# followLineSensor.net
KiCad netlist of a schematic drawn in EAGLE
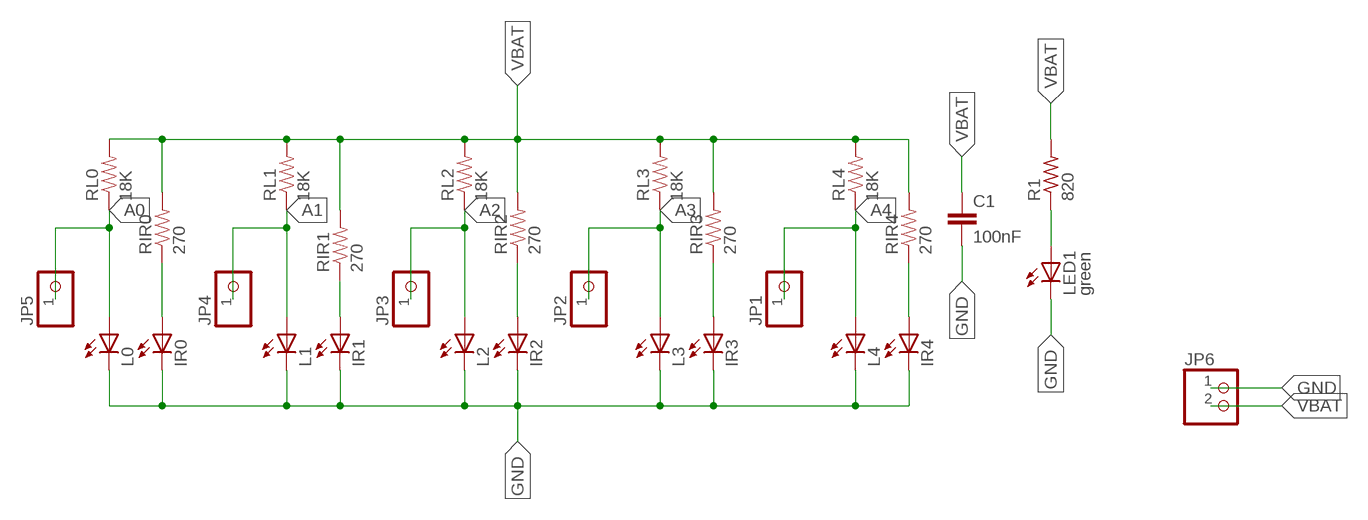
[diagram p0: schematic, sheet 1]

(export (version "E")
  (design (tool "Eeschema 10.0.6"))
  (components
    (comp (ref "C1")
      (value "100nF")
      (footprint "eagle-import:C0805")
      (libsource (lib "eagle-import") (part "C-EUC0805"))
    )
    (comp (ref "IR0")
      (value "LED5MM")
      (footprint "eagle-import:LED5MM")
      (libsource (lib "eagle-import") (part "LED5MM"))
    )
    (comp (ref "IR1")
      (value "LED5MM")
      (footprint "eagle-import:LED5MM")
      (libsource (lib "eagle-import") (part "LED5MM"))
    )
    (comp (ref "IR2")
      (value "LED5MM")
      (footprint "eagle-import:LED5MM")
      (libsource (lib "eagle-import") (part "LED5MM"))
    )
    (comp (ref "IR3")
      (value "LED5MM")
      (footprint "eagle-import:LED5MM")
      (libsource (lib "eagle-import") (part "LED5MM"))
    )
    (comp (ref "IR4")
      (value "LED5MM")
      (footprint "eagle-import:LED5MM")
      (libsource (lib "eagle-import") (part "LED5MM"))
    )
    (comp (ref "JP1")
      (value "PINHD-1X1")
      (footprint "eagle-import:1X01")
      (libsource (lib "eagle-import") (part "PINHD-1X1"))
    )
    (comp (ref "JP2")
      (value "PINHD-1X1")
      (footprint "eagle-import:1X01")
      (libsource (lib "eagle-import") (part "PINHD-1X1"))
    )
    (comp (ref "JP3")
      (value "PINHD-1X1")
      (footprint "eagle-import:1X01")
      (libsource (lib "eagle-import") (part "PINHD-1X1"))
    )
    (comp (ref "JP4")
      (value "PINHD-1X1")
      (footprint "eagle-import:1X01")
      (libsource (lib "eagle-import") (part "PINHD-1X1"))
    )
    (comp (ref "JP5")
      (value "PINHD-1X1")
      (footprint "eagle-import:1X01")
      (libsource (lib "eagle-import") (part "PINHD-1X1"))
    )
    (comp (ref "JP6")
      (value "PINHD-1X2")
      (footprint "eagle-import:1X02")
      (libsource (lib "eagle-import") (part "PINHD-1X2"))
    )
    (comp (ref "L0")
      (value "LED5MM")
      (footprint "eagle-import:LED5MM")
      (libsource (lib "eagle-import") (part "LED5MM"))
    )
    (comp (ref "L1")
      (value "LED5MM")
      (footprint "eagle-import:LED5MM")
      (libsource (lib "eagle-import") (part "LED5MM"))
    )
    (comp (ref "L2")
      (value "LED5MM")
      (footprint "eagle-import:LED5MM")
      (libsource (lib "eagle-import") (part "LED5MM"))
    )
    (comp (ref "L3")
      (value "LED5MM")
      (footprint "eagle-import:LED5MM")
      (libsource (lib "eagle-import") (part "LED5MM"))
    )
    (comp (ref "L4")
      (value "LED5MM")
      (footprint "eagle-import:LED5MM")
      (libsource (lib "eagle-import") (part "LED5MM"))
    )
    (comp (ref "LED1")
      (value "green")
      (footprint "eagle-import:SML0805")
      (libsource (lib "eagle-import") (part "LEDSML0805"))
    )
    (comp (ref "R1")
      (value "820")
      (footprint "eagle-import:R0805")
      (libsource (lib "eagle-import") (part "R-US_R0805"))
    )
    (comp (ref "RIR0")
      (value "270")
      (footprint "eagle-import:1206")
      (libsource (lib "eagle-import") (part "RESISTOR1206"))
    )
    (comp (ref "RIR1")
      (value "270")
      (footprint "eagle-import:1206")
      (libsource (lib "eagle-import") (part "RESISTOR1206"))
    )
    (comp (ref "RIR2")
      (value "270")
      (footprint "eagle-import:1206")
      (libsource (lib "eagle-import") (part "RESISTOR1206"))
    )
    (comp (ref "RIR3")
      (value "270")
      (footprint "eagle-import:1206")
      (libsource (lib "eagle-import") (part "RESISTOR1206"))
    )
    (comp (ref "RIR4")
      (value "270")
      (footprint "eagle-import:1206")
      (libsource (lib "eagle-import") (part "RESISTOR1206"))
    )
    (comp (ref "RL0")
      (value "18K")
      (footprint "eagle-import:1206")
      (libsource (lib "eagle-import") (part "RESISTOR1206"))
    )
    (comp (ref "RL1")
      (value "18K")
      (footprint "eagle-import:1206")
      (libsource (lib "eagle-import") (part "RESISTOR1206"))
    )
    (comp (ref "RL2")
      (value "18K")
      (footprint "eagle-import:1206")
      (libsource (lib "eagle-import") (part "RESISTOR1206"))
    )
    (comp (ref "RL3")
      (value "18K")
      (footprint "eagle-import:1206")
      (libsource (lib "eagle-import") (part "RESISTOR1206"))
    )
    (comp (ref "RL4")
      (value "18K")
      (footprint "eagle-import:1206")
      (libsource (lib "eagle-import") (part "RESISTOR1206"))
    )
  )
  (nets
    (net (code "1") (name "A0") (class "Default")
      (node (ref "JP5") (pin "1") (pinfunction "1_1") (pintype "passive"))
      (node (ref "L0") (pin "A") (pinfunction "A_A") (pintype "passive"))
      (node (ref "RL0") (pin "1") (pinfunction "1_1") (pintype "passive"))
    )
    (net (code "2") (name "A1") (class "Default")
      (node (ref "JP4") (pin "1") (pinfunction "1_1") (pintype "passive"))
      (node (ref "L1") (pin "A") (pinfunction "A_A") (pintype "passive"))
      (node (ref "RL1") (pin "1") (pinfunction "1_1") (pintype "passive"))
    )
    (net (code "3") (name "A2") (class "Default")
      (node (ref "JP3") (pin "1") (pinfunction "1_1") (pintype "passive"))
      (node (ref "L2") (pin "A") (pinfunction "A_A") (pintype "passive"))
      (node (ref "RL2") (pin "1") (pinfunction "1_1") (pintype "passive"))
    )
    (net (code "4") (name "A3") (class "Default")
      (node (ref "JP2") (pin "1") (pinfunction "1_1") (pintype "passive"))
      (node (ref "L3") (pin "A") (pinfunction "A_A") (pintype "passive"))
      (node (ref "RL3") (pin "1") (pinfunction "1_1") (pintype "passive"))
    )
    (net (code "5") (name "A4") (class "Default")
      (node (ref "JP1") (pin "1") (pinfunction "1_1") (pintype "passive"))
      (node (ref "L4") (pin "A") (pinfunction "A_A") (pintype "passive"))
      (node (ref "RL4") (pin "1") (pinfunction "1_1") (pintype "passive"))
    )
    (net (code "6") (name "GND") (class "Default")
      (node (ref "C1") (pin "2") (pinfunction "2_2") (pintype "passive"))
      (node (ref "IR0") (pin "K") (pinfunction "C_K") (pintype "passive"))
      (node (ref "IR1") (pin "K") (pinfunction "C_K") (pintype "passive"))
      (node (ref "IR2") (pin "K") (pinfunction "C_K") (pintype "passive"))
      (node (ref "IR3") (pin "K") (pinfunction "C_K") (pintype "passive"))
      (node (ref "IR4") (pin "K") (pinfunction "C_K") (pintype "passive"))
      (node (ref "JP6") (pin "1") (pinfunction "1_1") (pintype "passive"))
      (node (ref "L0") (pin "K") (pinfunction "C_K") (pintype "passive"))
      (node (ref "L1") (pin "K") (pinfunction "C_K") (pintype "passive"))
      (node (ref "L2") (pin "K") (pinfunction "C_K") (pintype "passive"))
      (node (ref "L3") (pin "K") (pinfunction "C_K") (pintype "passive"))
      (node (ref "L4") (pin "K") (pinfunction "C_K") (pintype "passive"))
      (node (ref "LED1") (pin "C") (pinfunction "C_C") (pintype "passive"))
    )
    (net (code "7") (name "Net-(IR0-PadA)") (class "Default")
      (node (ref "IR0") (pin "A") (pinfunction "A_A") (pintype "passive"))
      (node (ref "RIR0") (pin "1") (pinfunction "1_1") (pintype "passive"))
    )
    (net (code "8") (name "Net-(IR1-PadA)") (class "Default")
      (node (ref "IR1") (pin "A") (pinfunction "A_A") (pintype "passive"))
      (node (ref "RIR1") (pin "1") (pinfunction "1_1") (pintype "passive"))
    )
    (net (code "9") (name "Net-(IR2-PadA)") (class "Default")
      (node (ref "IR2") (pin "A") (pinfunction "A_A") (pintype "passive"))
      (node (ref "RIR2") (pin "1") (pinfunction "1_1") (pintype "passive"))
    )
    (net (code "10") (name "Net-(IR3-PadA)") (class "Default")
      (node (ref "IR3") (pin "A") (pinfunction "A_A") (pintype "passive"))
      (node (ref "RIR3") (pin "1") (pinfunction "1_1") (pintype "passive"))
    )
    (net (code "11") (name "Net-(IR4-PadA)") (class "Default")
      (node (ref "IR4") (pin "A") (pinfunction "A_A") (pintype "passive"))
      (node (ref "RIR4") (pin "1") (pinfunction "1_1") (pintype "passive"))
    )
    (net (code "12") (name "Net-(LED1-PadA)") (class "Default")
      (node (ref "LED1") (pin "A") (pinfunction "A_A") (pintype "passive"))
      (node (ref "R1") (pin "1") (pinfunction "1_1") (pintype "passive"))
    )
    (net (code "13") (name "VBAT") (class "Default")
      (node (ref "C1") (pin "1") (pinfunction "1_1") (pintype "passive"))
      (node (ref "JP6") (pin "2") (pinfunction "2_2") (pintype "passive"))
      (node (ref "R1") (pin "2") (pinfunction "2_2") (pintype "passive"))
      (node (ref "RIR0") (pin "2") (pinfunction "2_2") (pintype "passive"))
      (node (ref "RIR1") (pin "2") (pinfunction "2_2") (pintype "passive"))
      (node (ref "RIR2") (pin "2") (pinfunction "2_2") (pintype "passive"))
      (node (ref "RIR3") (pin "2") (pinfunction "2_2") (pintype "passive"))
      (node (ref "RIR4") (pin "2") (pinfunction "2_2") (pintype "passive"))
      (node (ref "RL0") (pin "2") (pinfunction "2_2") (pintype "passive"))
      (node (ref "RL1") (pin "2") (pinfunction "2_2") (pintype "passive"))
      (node (ref "RL2") (pin "2") (pinfunction "2_2") (pintype "passive"))
      (node (ref "RL3") (pin "2") (pinfunction "2_2") (pintype "passive"))
      (node (ref "RL4") (pin "2") (pinfunction "2_2") (pintype "passive"))
    )
  )
)
